# ISO_SPI.net
KiCad netlist of a schematic drawn in Altium Designer
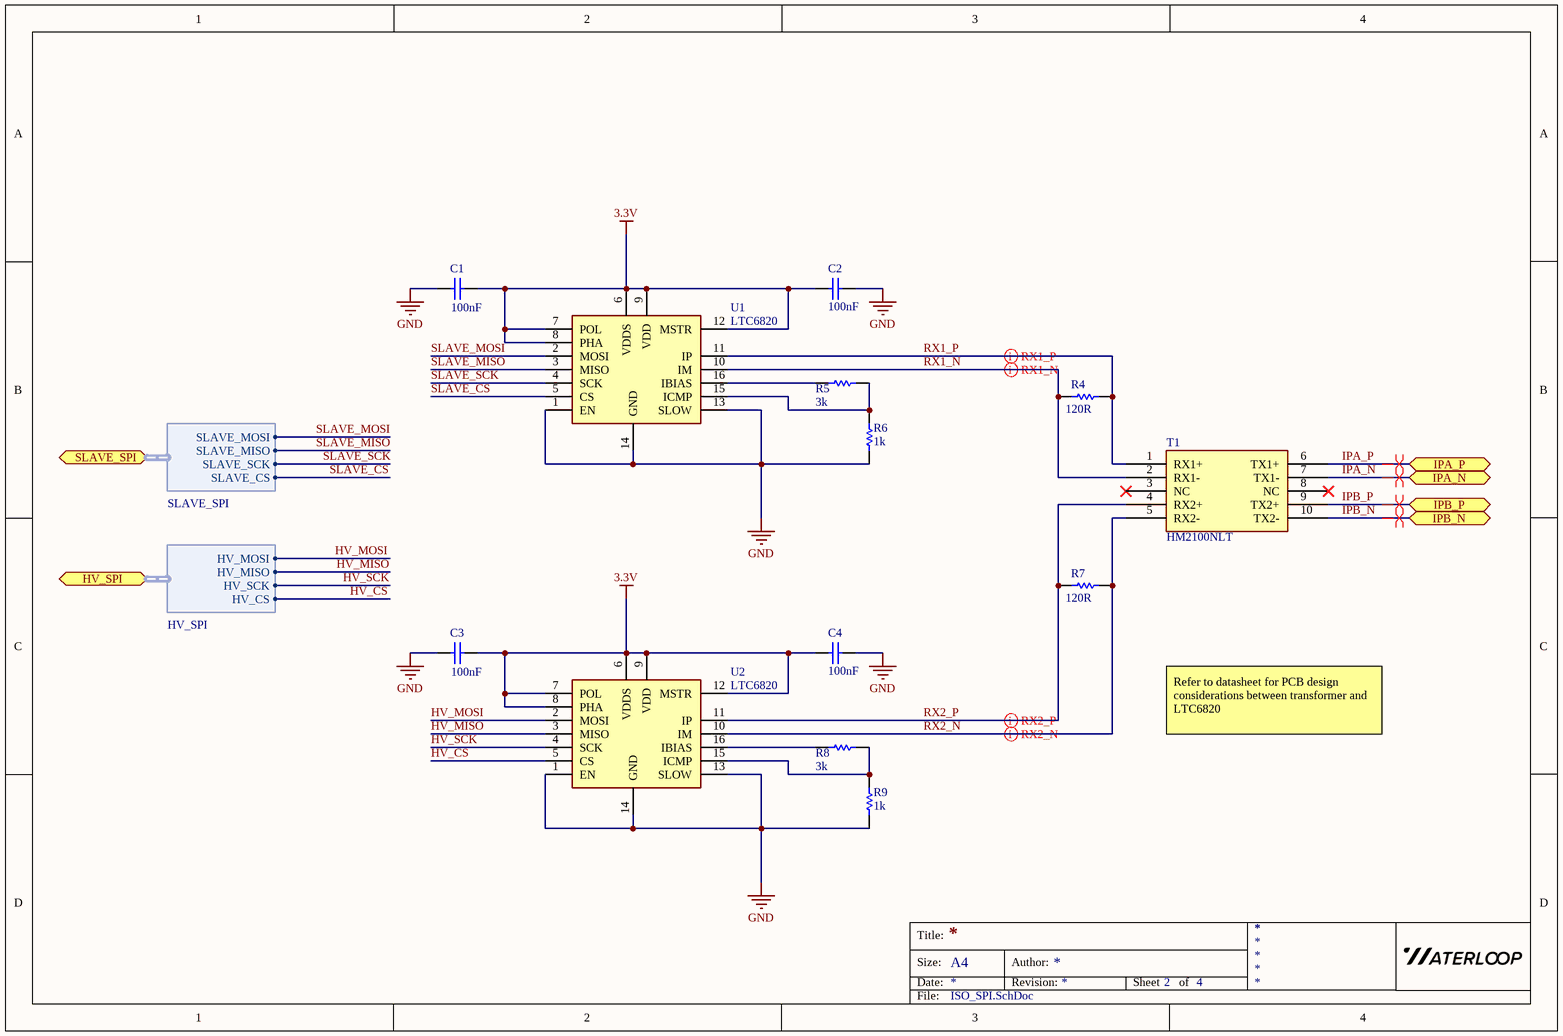
[diagram p0: ISO_SPI.SchDoc]

(export (version "E")
  (design (tool "Eeschema 10.0.6"))
  (components
    (comp (ref "C1")
      (value "100nF")
      (footprint "0805 - Capacitor")
      (description "C0805C103K8RAC7800. 10000pF ±10% 10V Ceramic Capacitor X7R 0805 (2012 Metric)")
      (fields
        (field (name "MANUFACTURER") "YAGEO")
        (field (name "MANUFACTURER PART NUMBER") "CC0805MRX7R9BB103")
      )
      (libsource (lib "General") (part "Capacitor - Nonpolarized"))
    )
    (comp (ref "C2")
      (value "100nF")
      (footprint "0805 - Capacitor")
      (description "C0805C103K8RAC7800. 10000pF ±10% 10V Ceramic Capacitor X7R 0805 (2012 Metric)")
      (fields
        (field (name "MANUFACTURER") "YAGEO")
        (field (name "MANUFACTURER PART NUMBER") "CC0805MRX7R9BB103")
      )
      (libsource (lib "General") (part "Capacitor - Nonpolarized"))
    )
    (comp (ref "C3")
      (value "100nF")
      (footprint "0805 - Capacitor")
      (description "C0805C103K8RAC7800. 10000pF ±10% 10V Ceramic Capacitor X7R 0805 (2012 Metric)")
      (fields
        (field (name "MANUFACTURER") "YAGEO")
        (field (name "MANUFACTURER PART NUMBER") "CC0805MRX7R9BB103")
      )
      (libsource (lib "General") (part "Capacitor - Nonpolarized"))
    )
    (comp (ref "C4")
      (value "100nF")
      (footprint "0805 - Capacitor")
      (description "C0805C103K8RAC7800. 10000pF ±10% 10V Ceramic Capacitor X7R 0805 (2012 Metric)")
      (fields
        (field (name "MANUFACTURER") "YAGEO")
        (field (name "MANUFACTURER PART NUMBER") "CC0805MRX7R9BB103")
      )
      (libsource (lib "General") (part "Capacitor - Nonpolarized"))
    )
    (comp (ref "R4")
      (value "120R")
      (footprint "0603 - Resistor")
      (fields
        (field (name "MANUFACTURER PART NUMBER") "RC0603FR-10120RL")
        (field (name "MANUFACTURER") "YAGEO")
        (field (name "Comment") "1%")
      )
      (libsource (lib "General") (part "Resistor"))
    )
    (comp (ref "R5")
      (value "3k")
      (footprint "0603 - Resistor")
      (fields
        (field (name "MANUFACTURER PART NUMBER") "RC0603FR-073KL")
        (field (name "MANUFACTURER") "YAGEO")
        (field (name "Comment") "1%")
      )
      (libsource (lib "General") (part "Resistor"))
    )
    (comp (ref "R6")
      (value "1k")
      (footprint "0603 - Resistor")
      (fields
        (field (name "MANUFACTURER PART NUMBER") "RC0603JR-071KL")
        (field (name "MANUFACTURER") "YAGEO")
        (field (name "Comment") "1%")
      )
      (libsource (lib "General") (part "Resistor"))
    )
    (comp (ref "R7")
      (value "120R")
      (footprint "0603 - Resistor")
      (fields
        (field (name "MANUFACTURER PART NUMBER") "RC0603FR-10120RL")
        (field (name "MANUFACTURER") "YAGEO")
        (field (name "Comment") "1%")
      )
      (libsource (lib "General") (part "Resistor"))
    )
    (comp (ref "R8")
      (value "3k")
      (footprint "0603 - Resistor")
      (fields
        (field (name "MANUFACTURER PART NUMBER") "RC0603FR-073KL")
        (field (name "MANUFACTURER") "YAGEO")
        (field (name "Comment") "1%")
      )
      (libsource (lib "General") (part "Resistor"))
    )
    (comp (ref "R9")
      (value "1k")
      (footprint "0603 - Resistor")
      (fields
        (field (name "MANUFACTURER PART NUMBER") "RC0603JR-071KL")
        (field (name "MANUFACTURER") "YAGEO")
        (field (name "Comment") "1%")
      )
      (libsource (lib "General") (part "Resistor"))
    )
    (comp (ref "T1")
      (value "HM2100NLT")
      (footprint "HM2100NLT")
      (description "Pulse Transformer 1:1 Surface Mount 150µH, 450µH")
      (fields (field (name "MANUFACTURER") "Pulse Electronics"))
      (libsource (lib "GeneralComponents") (part "HM2100NLT"))
    )
    (comp (ref "U1")
      (value "LTC6820")
      (footprint "LT6820_QFN")
      (fields
        (field (name "MANUFACTURER") "Analog Devices")
        (field (name "MANUFACTURER PART NUMBER") "LTC6820IMS#TRPBF")
      )
      (libsource (lib "BMS") (part "LTC6820"))
    )
    (comp (ref "U2")
      (value "LTC6820")
      (footprint "LT6820_QFN")
      (fields
        (field (name "MANUFACTURER") "Analog Devices")
        (field (name "MANUFACTURER PART NUMBER") "LTC6820IMS#TRPBF")
      )
      (libsource (lib "BMS") (part "LTC6820"))
    )
  )
  (nets
    (net (code "3") (name "/HV_CS") (class "Default")
      (node (ref "U2") (pin "5") (pinfunction "CS_5") (pintype "passive"))
    )
    (net (code "4") (name "/HV_MISO") (class "Default")
      (node (ref "U2") (pin "3") (pinfunction "MISO_3") (pintype "passive"))
    )
    (net (code "5") (name "/HV_MOSI") (class "Default")
      (node (ref "U2") (pin "2") (pinfunction "MOSI_2") (pintype "passive"))
    )
    (net (code "6") (name "/HV_SCK") (class "Default")
      (node (ref "U2") (pin "4") (pinfunction "SCK_4") (pintype "passive"))
    )
    (net (code "7") (name "/IPA_N") (class "Default")
      (node (ref "T1") (pin "7") (pinfunction "TX1-_7") (pintype "passive"))
    )
    (net (code "8") (name "/IPA_P") (class "Default")
      (node (ref "T1") (pin "6") (pinfunction "TX1+_6") (pintype "passive"))
    )
    (net (code "9") (name "/IPB_N") (class "Default")
      (node (ref "T1") (pin "10") (pinfunction "TX2-_10") (pintype "passive"))
    )
    (net (code "10") (name "/IPB_P") (class "Default")
      (node (ref "T1") (pin "9") (pinfunction "TX2+_9") (pintype "passive"))
    )
    (net (code "11") (name "/RX1_N") (class "Default")
      (node (ref "R4") (pin "1") (pinfunction "1_1") (pintype "passive"))
      (node (ref "T1") (pin "2") (pinfunction "RX1-_2") (pintype "passive"))
      (node (ref "U1") (pin "10") (pinfunction "IM_10") (pintype "passive"))
    )
    (net (code "12") (name "/RX1_P") (class "Default")
      (node (ref "R4") (pin "2") (pinfunction "2_2") (pintype "passive"))
      (node (ref "T1") (pin "1") (pinfunction "RX1+_1") (pintype "passive"))
      (node (ref "U1") (pin "11") (pinfunction "IP_11") (pintype "passive"))
    )
    (net (code "13") (name "/RX2_N") (class "Default")
      (node (ref "R7") (pin "2") (pinfunction "2_2") (pintype "passive"))
      (node (ref "T1") (pin "5") (pinfunction "RX2-_5") (pintype "passive"))
      (node (ref "U2") (pin "10") (pinfunction "IM_10") (pintype "passive"))
    )
    (net (code "14") (name "/RX2_P") (class "Default")
      (node (ref "R7") (pin "1") (pinfunction "1_1") (pintype "passive"))
      (node (ref "T1") (pin "4") (pinfunction "RX2+_4") (pintype "passive"))
      (node (ref "U2") (pin "11") (pinfunction "IP_11") (pintype "passive"))
    )
    (net (code "15") (name "/SLAVE_CS") (class "Default")
      (node (ref "U1") (pin "5") (pinfunction "CS_5") (pintype "passive"))
    )
    (net (code "16") (name "/SLAVE_MISO") (class "Default")
      (node (ref "U1") (pin "3") (pinfunction "MISO_3") (pintype "passive"))
    )
    (net (code "17") (name "/SLAVE_MOSI") (class "Default")
      (node (ref "U1") (pin "2") (pinfunction "MOSI_2") (pintype "passive"))
    )
    (net (code "18") (name "/SLAVE_SCK") (class "Default")
      (node (ref "U1") (pin "4") (pinfunction "SCK_4") (pintype "passive"))
    )
    (net (code "21") (name "3.3V") (class "Default")
      (node (ref "C1") (pin "2") (pinfunction "2_2") (pintype "passive"))
      (node (ref "C2") (pin "1") (pinfunction "1_1") (pintype "passive"))
      (node (ref "C3") (pin "2") (pinfunction "2_2") (pintype "passive"))
      (node (ref "C4") (pin "1") (pinfunction "1_1") (pintype "passive"))
      (node (ref "U1") (pin "12") (pinfunction "MSTR_12") (pintype "passive"))
      (node (ref "U1") (pin "6") (pinfunction "VDDS_6") (pintype "passive"))
      (node (ref "U1") (pin "7") (pinfunction "POL_7") (pintype "passive"))
      (node (ref "U1") (pin "8") (pinfunction "PHA_8") (pintype "passive"))
      (node (ref "U1") (pin "9") (pinfunction "VDD_9") (pintype "passive"))
      (node (ref "U2") (pin "12") (pinfunction "MSTR_12") (pintype "passive"))
      (node (ref "U2") (pin "6") (pinfunction "VDDS_6") (pintype "passive"))
      (node (ref "U2") (pin "7") (pinfunction "POL_7") (pintype "passive"))
      (node (ref "U2") (pin "8") (pinfunction "PHA_8") (pintype "passive"))
      (node (ref "U2") (pin "9") (pinfunction "VDD_9") (pintype "passive"))
    )
    (net (code "22") (name "GND") (class "Default")
      (node (ref "C1") (pin "1") (pinfunction "1_1") (pintype "passive"))
      (node (ref "C2") (pin "2") (pinfunction "2_2") (pintype "passive"))
      (node (ref "C3") (pin "1") (pinfunction "1_1") (pintype "passive"))
      (node (ref "C4") (pin "2") (pinfunction "2_2") (pintype "passive"))
      (node (ref "R6") (pin "1") (pinfunction "1_1") (pintype "passive"))
      (node (ref "R9") (pin "1") (pinfunction "1_1") (pintype "passive"))
      (node (ref "U1") (pin "1") (pinfunction "EN_1") (pintype "passive"))
      (node (ref "U1") (pin "13") (pinfunction "SLOW_13") (pintype "passive"))
      (node (ref "U1") (pin "14") (pinfunction "GND_14") (pintype "passive"))
      (node (ref "U2") (pin "1") (pinfunction "EN_1") (pintype "passive"))
      (node (ref "U2") (pin "13") (pinfunction "SLOW_13") (pintype "passive"))
      (node (ref "U2") (pin "14") (pinfunction "GND_14") (pintype "passive"))
    )
    (net (code "23") (name "Net-(U1-IBIAS)") (class "Default")
      (node (ref "R5") (pin "1") (pinfunction "1_1") (pintype "passive"))
      (node (ref "U1") (pin "16") (pinfunction "IBIAS_16") (pintype "passive"))
    )
    (net (code "24") (name "Net-(U1-ICMP)") (class "Default")
      (node (ref "R5") (pin "2") (pinfunction "2_2") (pintype "passive"))
      (node (ref "R6") (pin "2") (pinfunction "2_2") (pintype "passive"))
      (node (ref "U1") (pin "15") (pinfunction "ICMP_15") (pintype "passive"))
    )
    (net (code "25") (name "Net-(U2-IBIAS)") (class "Default")
      (node (ref "R8") (pin "1") (pinfunction "1_1") (pintype "passive"))
      (node (ref "U2") (pin "16") (pinfunction "IBIAS_16") (pintype "passive"))
    )
    (net (code "26") (name "Net-(U2-ICMP)") (class "Default")
      (node (ref "R8") (pin "2") (pinfunction "2_2") (pintype "passive"))
      (node (ref "R9") (pin "2") (pinfunction "2_2") (pintype "passive"))
      (node (ref "U2") (pin "15") (pinfunction "ICMP_15") (pintype "passive"))
    )
    (net (code "27") (name "unconnected-(T1-NC-Pad3)") (class "Default")
      (node (ref "T1") (pin "3") (pinfunction "NC_3") (pintype "passive+no_connect"))
    )
    (net (code "28") (name "unconnected-(T1-NC-Pad8)") (class "Default")
      (node (ref "T1") (pin "8") (pinfunction "NC_8") (pintype "passive+no_connect"))
    )
  )
)
